# Display.net
KiCad netlist of a schematic drawn in EAGLE
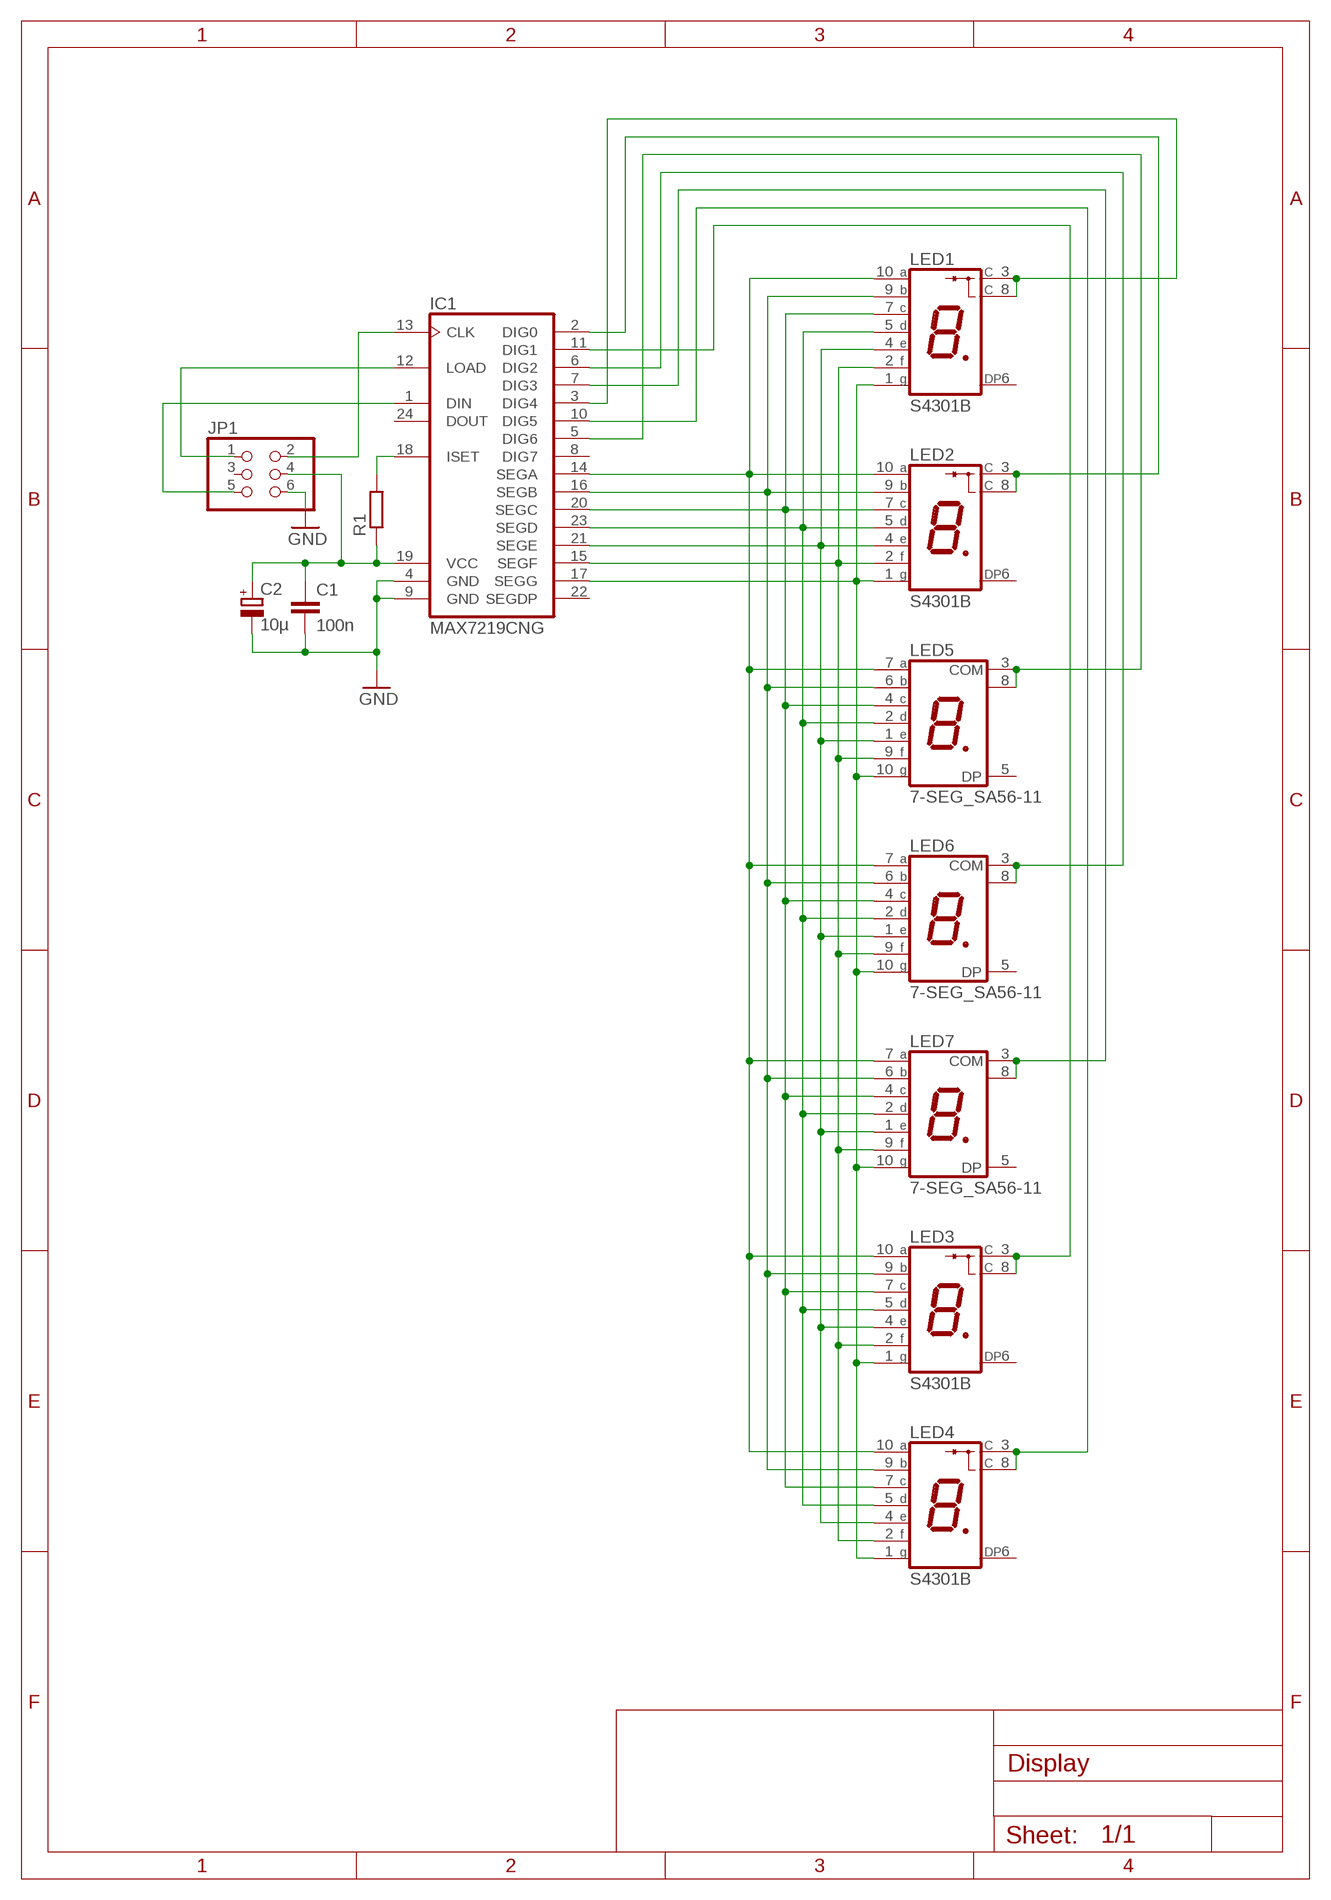
[diagram p0: schematic, sheet 1]

(export (version "E")
  (design (tool "Eeschema 10.0.6"))
  (components
    (comp (ref "C1")
      (value "100n")
      (footprint "eagle-import:C0805")
      (libsource (lib "eagle-import") (part "C-EUC0805"))
    )
    (comp (ref "C2")
      (value "10µ")
      (footprint "eagle-import:PANASONIC_B")
      (libsource (lib "eagle-import") (part "CPOL-EUB"))
    )
    (comp (ref "IC1")
      (value "MAX7219CNG")
      (footprint "eagle-import:DIL24-3")
      (libsource (lib "eagle-import") (part "MAX7219NGC"))
    )
    (comp (ref "JP1")
      (value "PINHD-2X03_2.54")
      (footprint "eagle-import:2X03")
      (libsource (lib "eagle-import") (part "PINHD-2X03_2.54"))
    )
    (comp (ref "LED1")
      (value "S4301B")
      (footprint "eagle-import:S4301B")
      (libsource (lib "eagle-import") (part "S4301B"))
    )
    (comp (ref "LED2")
      (value "S4301B")
      (footprint "eagle-import:S4301B")
      (libsource (lib "eagle-import") (part "S4301B"))
    )
    (comp (ref "LED3")
      (value "S4301B")
      (footprint "eagle-import:S4301B")
      (libsource (lib "eagle-import") (part "S4301B"))
    )
    (comp (ref "LED4")
      (value "S4301B")
      (footprint "eagle-import:S4301B")
      (libsource (lib "eagle-import") (part "S4301B"))
    )
    (comp (ref "LED5")
      (value "7-SEG_SA56-11")
      (footprint "eagle-import:SA56-11")
      (libsource (lib "eagle-import") (part "7-SEG_SA56-11"))
    )
    (comp (ref "LED6")
      (value "7-SEG_SA56-11")
      (footprint "eagle-import:SA56-11")
      (libsource (lib "eagle-import") (part "7-SEG_SA56-11"))
    )
    (comp (ref "LED7")
      (value "7-SEG_SA56-11")
      (footprint "eagle-import:SA56-11")
      (libsource (lib "eagle-import") (part "7-SEG_SA56-11"))
    )
    (comp (ref "R1")
      (value "R-EU_R0805")
      (footprint "eagle-import:R0805")
      (libsource (lib "eagle-import") (part "R-EU_R0805"))
    )
  )
  (nets
    (net (code "1") (name "GND") (class "Default")
      (node (ref "C1") (pin "2") (pinfunction "2_2") (pintype "passive"))
      (node (ref "C2") (pin "-") (pinfunction "-_-") (pintype "passive"))
      (node (ref "IC1") (pin "4") (pinfunction "GND_4") (pintype "power_in"))
      (node (ref "IC1") (pin "9") (pinfunction "GND_9") (pintype "power_in"))
      (node (ref "JP1") (pin "6") (pinfunction "6_6") (pintype "passive"))
    )
    (net (code "2") (name "Net-(IC1-CLK)") (class "Default")
      (node (ref "IC1") (pin "13") (pinfunction "CLK_13") (pintype "input"))
      (node (ref "JP1") (pin "2") (pinfunction "2_2") (pintype "passive"))
    )
    (net (code "3") (name "Net-(IC1-DIG0)") (class "Default")
      (node (ref "IC1") (pin "2") (pinfunction "DIG0_2") (pintype "output"))
      (node (ref "LED2") (pin "3") (pinfunction "C_3") (pintype "passive"))
      (node (ref "LED2") (pin "8") (pinfunction "C_8") (pintype "passive"))
    )
    (net (code "4") (name "Net-(IC1-DIG1)") (class "Default")
      (node (ref "IC1") (pin "11") (pinfunction "DIG1_11") (pintype "output"))
      (node (ref "LED3") (pin "3") (pinfunction "C_3") (pintype "passive"))
      (node (ref "LED3") (pin "8") (pinfunction "C_8") (pintype "passive"))
    )
    (net (code "5") (name "Net-(IC1-DIG2)") (class "Default")
      (node (ref "IC1") (pin "6") (pinfunction "DIG2_6") (pintype "output"))
      (node (ref "LED6") (pin "3") (pinfunction "COM_3") (pintype "passive"))
      (node (ref "LED6") (pin "8") (pinfunction "COM_8") (pintype "passive"))
    )
    (net (code "6") (name "Net-(IC1-DIG3)") (class "Default")
      (node (ref "IC1") (pin "7") (pinfunction "DIG3_7") (pintype "output"))
      (node (ref "LED7") (pin "3") (pinfunction "COM_3") (pintype "passive"))
      (node (ref "LED7") (pin "8") (pinfunction "COM_8") (pintype "passive"))
    )
    (net (code "7") (name "Net-(IC1-DIG4)") (class "Default")
      (node (ref "IC1") (pin "3") (pinfunction "DIG4_3") (pintype "output"))
      (node (ref "LED1") (pin "3") (pinfunction "C_3") (pintype "passive"))
      (node (ref "LED1") (pin "8") (pinfunction "C_8") (pintype "passive"))
    )
    (net (code "8") (name "Net-(IC1-DIG5)") (class "Default")
      (node (ref "IC1") (pin "10") (pinfunction "DIG5_10") (pintype "output"))
      (node (ref "LED4") (pin "3") (pinfunction "C_3") (pintype "passive"))
      (node (ref "LED4") (pin "8") (pinfunction "C_8") (pintype "passive"))
    )
    (net (code "9") (name "Net-(IC1-DIG6)") (class "Default")
      (node (ref "IC1") (pin "5") (pinfunction "DIG6_5") (pintype "output"))
      (node (ref "LED5") (pin "3") (pinfunction "COM_3") (pintype "passive"))
      (node (ref "LED5") (pin "8") (pinfunction "COM_8") (pintype "passive"))
    )
    (net (code "10") (name "Net-(IC1-DIN)") (class "Default")
      (node (ref "IC1") (pin "1") (pinfunction "DIN_1") (pintype "input"))
      (node (ref "JP1") (pin "5") (pinfunction "5_5") (pintype "passive"))
    )
    (net (code "11") (name "Net-(IC1-ISET)") (class "Default")
      (node (ref "IC1") (pin "18") (pinfunction "ISET_18") (pintype "input"))
      (node (ref "R1") (pin "2") (pinfunction "2_2") (pintype "passive"))
    )
    (net (code "12") (name "Net-(IC1-LOAD)") (class "Default")
      (node (ref "IC1") (pin "12") (pinfunction "LOAD_12") (pintype "input"))
      (node (ref "JP1") (pin "1") (pinfunction "1_1") (pintype "passive"))
    )
    (net (code "13") (name "Net-(IC1-SEGA)") (class "Default")
      (node (ref "IC1") (pin "14") (pinfunction "SEGA_14") (pintype "output"))
      (node (ref "LED1") (pin "10") (pinfunction "A_10") (pintype "passive"))
      (node (ref "LED2") (pin "10") (pinfunction "A_10") (pintype "passive"))
      (node (ref "LED3") (pin "10") (pinfunction "A_10") (pintype "passive"))
      (node (ref "LED4") (pin "10") (pinfunction "A_10") (pintype "passive"))
      (node (ref "LED5") (pin "7") (pinfunction "A_7") (pintype "passive"))
      (node (ref "LED6") (pin "7") (pinfunction "A_7") (pintype "passive"))
      (node (ref "LED7") (pin "7") (pinfunction "A_7") (pintype "passive"))
    )
    (net (code "14") (name "Net-(IC1-SEGB)") (class "Default")
      (node (ref "IC1") (pin "16") (pinfunction "SEGB_16") (pintype "output"))
      (node (ref "LED1") (pin "9") (pinfunction "B_9") (pintype "passive"))
      (node (ref "LED2") (pin "9") (pinfunction "B_9") (pintype "passive"))
      (node (ref "LED3") (pin "9") (pinfunction "B_9") (pintype "passive"))
      (node (ref "LED4") (pin "9") (pinfunction "B_9") (pintype "passive"))
      (node (ref "LED5") (pin "6") (pinfunction "B_6") (pintype "passive"))
      (node (ref "LED6") (pin "6") (pinfunction "B_6") (pintype "passive"))
      (node (ref "LED7") (pin "6") (pinfunction "B_6") (pintype "passive"))
    )
    (net (code "15") (name "Net-(IC1-SEGC)") (class "Default")
      (node (ref "IC1") (pin "20") (pinfunction "SEGC_20") (pintype "output"))
      (node (ref "LED1") (pin "7") (pinfunction "C_7") (pintype "passive"))
      (node (ref "LED2") (pin "7") (pinfunction "C_7") (pintype "passive"))
      (node (ref "LED3") (pin "7") (pinfunction "C_7") (pintype "passive"))
      (node (ref "LED4") (pin "7") (pinfunction "C_7") (pintype "passive"))
      (node (ref "LED5") (pin "4") (pinfunction "C_4") (pintype "passive"))
      (node (ref "LED6") (pin "4") (pinfunction "C_4") (pintype "passive"))
      (node (ref "LED7") (pin "4") (pinfunction "C_4") (pintype "passive"))
    )
    (net (code "16") (name "Net-(IC1-SEGD)") (class "Default")
      (node (ref "IC1") (pin "23") (pinfunction "SEGD_23") (pintype "output"))
      (node (ref "LED1") (pin "5") (pinfunction "D_5") (pintype "passive"))
      (node (ref "LED2") (pin "5") (pinfunction "D_5") (pintype "passive"))
      (node (ref "LED3") (pin "5") (pinfunction "D_5") (pintype "passive"))
      (node (ref "LED4") (pin "5") (pinfunction "D_5") (pintype "passive"))
      (node (ref "LED5") (pin "2") (pinfunction "D_2") (pintype "passive"))
      (node (ref "LED6") (pin "2") (pinfunction "D_2") (pintype "passive"))
      (node (ref "LED7") (pin "2") (pinfunction "D_2") (pintype "passive"))
    )
    (net (code "17") (name "Net-(IC1-SEGE)") (class "Default")
      (node (ref "IC1") (pin "21") (pinfunction "SEGE_21") (pintype "output"))
      (node (ref "LED1") (pin "4") (pinfunction "E_4") (pintype "passive"))
      (node (ref "LED2") (pin "4") (pinfunction "E_4") (pintype "passive"))
      (node (ref "LED3") (pin "4") (pinfunction "E_4") (pintype "passive"))
      (node (ref "LED4") (pin "4") (pinfunction "E_4") (pintype "passive"))
      (node (ref "LED5") (pin "1") (pinfunction "E_1") (pintype "passive"))
      (node (ref "LED6") (pin "1") (pinfunction "E_1") (pintype "passive"))
      (node (ref "LED7") (pin "1") (pinfunction "E_1") (pintype "passive"))
    )
    (net (code "18") (name "Net-(IC1-SEGF)") (class "Default")
      (node (ref "IC1") (pin "15") (pinfunction "SEGF_15") (pintype "output"))
      (node (ref "LED1") (pin "2") (pinfunction "F_2") (pintype "passive"))
      (node (ref "LED2") (pin "2") (pinfunction "F_2") (pintype "passive"))
      (node (ref "LED3") (pin "2") (pinfunction "F_2") (pintype "passive"))
      (node (ref "LED4") (pin "2") (pinfunction "F_2") (pintype "passive"))
      (node (ref "LED5") (pin "9") (pinfunction "F_9") (pintype "passive"))
      (node (ref "LED6") (pin "9") (pinfunction "F_9") (pintype "passive"))
      (node (ref "LED7") (pin "9") (pinfunction "F_9") (pintype "passive"))
    )
    (net (code "19") (name "Net-(IC1-SEGG)") (class "Default")
      (node (ref "IC1") (pin "17") (pinfunction "SEGG_17") (pintype "output"))
      (node (ref "LED1") (pin "1") (pinfunction "G_1") (pintype "passive"))
      (node (ref "LED2") (pin "1") (pinfunction "G_1") (pintype "passive"))
      (node (ref "LED3") (pin "1") (pinfunction "G_1") (pintype "passive"))
      (node (ref "LED4") (pin "1") (pinfunction "G_1") (pintype "passive"))
      (node (ref "LED5") (pin "10") (pinfunction "G_10") (pintype "passive"))
      (node (ref "LED6") (pin "10") (pinfunction "G_10") (pintype "passive"))
      (node (ref "LED7") (pin "10") (pinfunction "G_10") (pintype "passive"))
    )
    (net (code "20") (name "Net-(IC1-VCC)") (class "Default")
      (node (ref "C1") (pin "1") (pinfunction "1_1") (pintype "passive"))
      (node (ref "C2") (pin "+") (pinfunction "+_+") (pintype "passive"))
      (node (ref "IC1") (pin "19") (pinfunction "VCC_19") (pintype "power_in"))
      (node (ref "JP1") (pin "4") (pinfunction "4_4") (pintype "passive"))
      (node (ref "R1") (pin "1") (pinfunction "1_1") (pintype "passive"))
    )
    (net (code "21") (name "unconnected-(IC1-DIG7-Pad8)") (class "Default")
      (node (ref "IC1") (pin "8") (pinfunction "DIG7_8") (pintype "output"))
    )
    (net (code "22") (name "unconnected-(IC1-DOUT-Pad24)") (class "Default")
      (node (ref "IC1") (pin "24") (pinfunction "DOUT_24") (pintype "output"))
    )
    (net (code "23") (name "unconnected-(IC1-SEGDP-Pad22)") (class "Default")
      (node (ref "IC1") (pin "22") (pinfunction "SEGDP_22") (pintype "output"))
    )
    (net (code "24") (name "unconnected-(JP1-Pad3)") (class "Default")
      (node (ref "JP1") (pin "3") (pinfunction "3_3") (pintype "passive"))
    )
    (net (code "25") (name "unconnected-(LED1-DP-Pad6)") (class "Default")
      (node (ref "LED1") (pin "6") (pinfunction "DP_6") (pintype "passive"))
    )
    (net (code "26") (name "unconnected-(LED2-DP-Pad6)") (class "Default")
      (node (ref "LED2") (pin "6") (pinfunction "DP_6") (pintype "passive"))
    )
    (net (code "27") (name "unconnected-(LED3-DP-Pad6)") (class "Default")
      (node (ref "LED3") (pin "6") (pinfunction "DP_6") (pintype "passive"))
    )
    (net (code "28") (name "unconnected-(LED4-DP-Pad6)") (class "Default")
      (node (ref "LED4") (pin "6") (pinfunction "DP_6") (pintype "passive"))
    )
    (net (code "29") (name "unconnected-(LED5-DP-Pad5)") (class "Default")
      (node (ref "LED5") (pin "5") (pinfunction "DP_5") (pintype "passive"))
    )
    (net (code "30") (name "unconnected-(LED6-DP-Pad5)") (class "Default")
      (node (ref "LED6") (pin "5") (pinfunction "DP_5") (pintype "passive"))
    )
    (net (code "31") (name "unconnected-(LED7-DP-Pad5)") (class "Default")
      (node (ref "LED7") (pin "5") (pinfunction "DP_5") (pintype "passive"))
    )
  )
)
